# Micro_Controller.net
KiCad netlist of a schematic drawn in Altium Designer
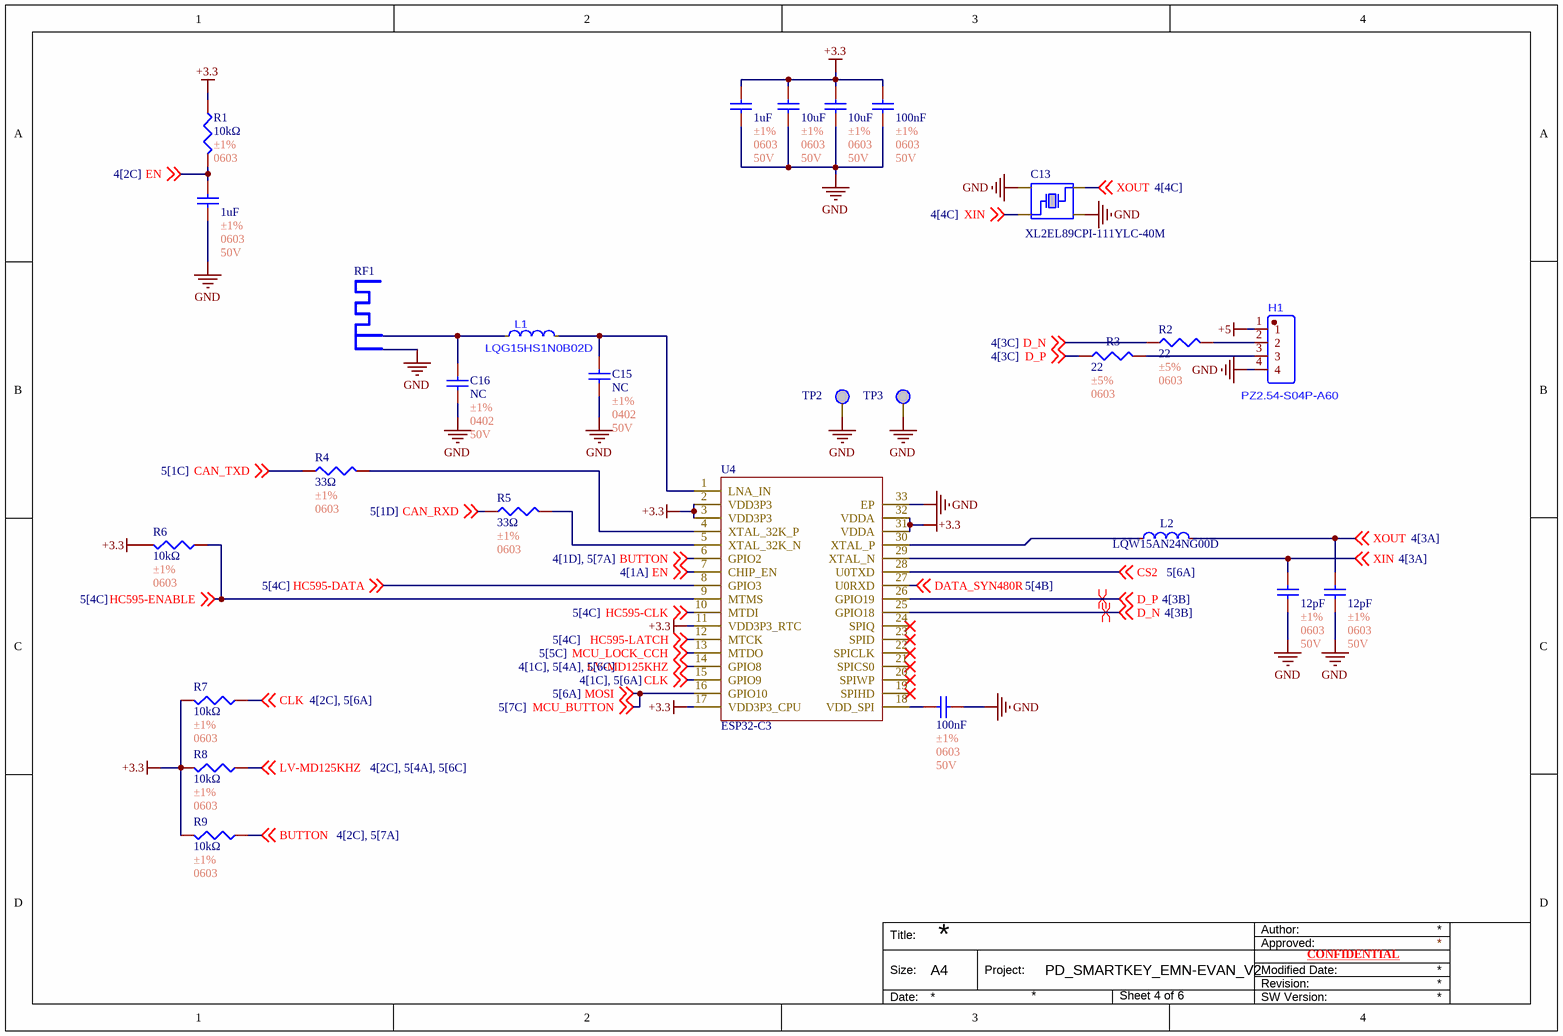
[diagram p0: Micro Controller.SchDoc]

(export (version "E")
  (design (tool "Eeschema 10.0.6"))
  (components
    (comp (ref "C9")
      (value "1uF")
      (footprint "C0603")
      (description "50V 10pF NP0 ±1% 0402 Multilayer Ceramic Capacitors MLCC - SMD/SMT ROHS")
      (fields
        (field (name "MANUFACTURER") "YAGEO")
        (field (name "MFR. PART #") "CC0402FRNPO9BN100")
        (field (name "TOLERANCE") "±1%")
        (field (name "PACKAGE") "0603")
        (field (name "VOLTAGE RATING") "50V")
      )
      (libsource (lib "Capital") (part "C0603_1uF_±1%"))
    )
    (comp (ref "C10")
      (value "10uF")
      (footprint "C0603")
      (description "50V 10pF NP0 ±1% 0402 Multilayer Ceramic Capacitors MLCC - SMD/SMT ROHS")
      (fields
        (field (name "MANUFACTURER") "YAGEO")
        (field (name "MFR. PART #") "CC0402FRNPO9BN100")
        (field (name "TOLERANCE") "±1%")
        (field (name "PACKAGE") "0603")
        (field (name "VOLTAGE RATING") "50V")
      )
      (libsource (lib "Capital") (part "C0603_10uF_±1%"))
    )
    (comp (ref "C11")
      (value "10uF")
      (footprint "C0603")
      (description "50V 10pF NP0 ±1% 0402 Multilayer Ceramic Capacitors MLCC - SMD/SMT ROHS")
      (fields
        (field (name "MANUFACTURER") "YAGEO")
        (field (name "MFR. PART #") "CC0402FRNPO9BN100")
        (field (name "TOLERANCE") "±1%")
        (field (name "PACKAGE") "0603")
        (field (name "VOLTAGE RATING") "50V")
      )
      (libsource (lib "Capital") (part "C0603_10uF_±1%"))
    )
    (comp (ref "C12")
      (value "100nF")
      (footprint "C0603")
      (description "50V 10pF NP0 ±1% 0402 Multilayer Ceramic Capacitors MLCC - SMD/SMT ROHS")
      (fields
        (field (name "MANUFACTURER") "YAGEO")
        (field (name "MFR. PART #") "CC0402FRNPO9BN100")
        (field (name "TOLERANCE") "±1%")
        (field (name "PACKAGE") "0603")
        (field (name "VOLTAGE RATING") "50V")
      )
      (libsource (lib "Capital") (part "C0603_100nF_±1%"))
    )
    (comp (ref "C13")
      (value "XL2EL89CPI-111YLC-40M")
      (footprint "XL2EL89CPI-111YLC-40M")
      (description "Crystal Oscillator 15pF SMD3225-4P Crystals RoHS")
      (fields (field (name "MANUFACTURER") "YXC Crystal Oscillators") (field (name "LCSC PART #") "C5444549"))
      (libsource (lib "Oscillator") (part "XL2EL89CPI-111YLC-40M"))
    )
    (comp (ref "C14")
      (value "1uF")
      (footprint "C0603")
      (description "50V 10pF NP0 ±1% 0402 Multilayer Ceramic Capacitors MLCC - SMD/SMT ROHS")
      (fields
        (field (name "MANUFACTURER") "YAGEO")
        (field (name "MFR. PART #") "CC0402FRNPO9BN100")
        (field (name "TOLERANCE") "±1%")
        (field (name "PACKAGE") "0603")
        (field (name "VOLTAGE RATING") "50V")
      )
      (libsource (lib "Capital") (part "C0603_1uF_±1%"))
    )
    (comp (ref "C15")
      (value "NC")
      (footprint "C0402")
      (fields
        (field (name "MANUFACTURER") "YAGEO")
        (field (name "MFR. PART #") "CC0402FRNPO9BN100")
        (field (name "LCSC PART #") "C513681")
        (field (name "TOLERANCE") "±1%")
        (field (name "PACKAGE") "0402")
        (field (name "VOLTAGE RATING") "50V")
      )
      (libsource (lib "Capital") (part "C0402_NC_±1%"))
    )
    (comp (ref "C16")
      (value "NC")
      (footprint "C0402")
      (fields
        (field (name "MANUFACTURER") "YAGEO")
        (field (name "MFR. PART #") "CC0402FRNPO9BN100")
        (field (name "LCSC PART #") "C513681")
        (field (name "TOLERANCE") "±1%")
        (field (name "PACKAGE") "0402")
        (field (name "VOLTAGE RATING") "50V")
      )
      (libsource (lib "Capital") (part "C0402_NC_±1%"))
    )
    (comp (ref "C17")
      (value "12pF")
      (footprint "C0603")
      (description "50V 10pF NP0 ±1% 0402 Multilayer Ceramic Capacitors MLCC - SMD/SMT ROHS")
      (fields
        (field (name "MANUFACTURER") "YAGEO")
        (field (name "MFR. PART #") "CC0402FRNPO9BN100")
        (field (name "TOLERANCE") "±1%")
        (field (name "PACKAGE") "0603")
        (field (name "VOLTAGE RATING") "50V")
      )
      (libsource (lib "Capital") (part "C0603_12pF_±1%"))
    )
    (comp (ref "C18")
      (value "12pF")
      (footprint "C0603")
      (description "50V 10pF NP0 ±1% 0402 Multilayer Ceramic Capacitors MLCC - SMD/SMT ROHS")
      (fields
        (field (name "MANUFACTURER") "YAGEO")
        (field (name "MFR. PART #") "CC0402FRNPO9BN100")
        (field (name "TOLERANCE") "±1%")
        (field (name "PACKAGE") "0603")
        (field (name "VOLTAGE RATING") "50V")
      )
      (libsource (lib "Capital") (part "C0603_12pF_±1%"))
    )
    (comp (ref "C19")
      (value "100nF")
      (footprint "C0603")
      (description "50V 10pF NP0 ±1% 0402 Multilayer Ceramic Capacitors MLCC - SMD/SMT ROHS")
      (fields
        (field (name "MANUFACTURER") "YAGEO")
        (field (name "MFR. PART #") "CC0402FRNPO9BN100")
        (field (name "TOLERANCE") "±1%")
        (field (name "PACKAGE") "0603")
        (field (name "VOLTAGE RATING") "50V")
      )
      (libsource (lib "Capital") (part "C0603_100nF_±1%"))
    )
    (comp (ref "H1")
      (value "PZ2.54-S04P-A60")
      (footprint "J_4P_XH2.54")
      (fields (field (name "MANUFACTURER") "JXTCONN") (field (name "LCSC PART #") "C42431795"))
      (libsource (lib "Header") (part "J_4P_XH2.54"))
    )
    (comp (ref "L1")
      (value "LQG15HS1N0B02D")
      (footprint "L0402_1nH")
      (description "FIXED IND 1nH 1A 70mΩ 0402")
      (fields (field (name "MANUFACTURER") "muRata") (field (name "LCSC PART #") "C162538"))
      (libsource (lib "Inductor") (part "L0402_1nH"))
    )
    (comp (ref "L2")
      (value "LQW15AN24NG00D")
      (footprint "LQW15AN24NG00D")
      (description "FIXED IND 24nH 280mA 520mΩ 0402")
      (fields (field (name "MANUFACTURER") "muRata") (field (name "LCSC PART #") "C167472"))
      (libsource (lib "Inductor") (part "LQW15AN24NG00D"))
    )
    (comp (ref "R1")
      (value "10kΩ")
      (footprint "R0603")
      (description "62.5mW Thick Film Resistor 50V ±1% ±200ppm/℃ 10Ω 0402 Chip Resistor - Surface Mount ROHS")
      (fields
        (field (name "MANUFACTURER") "YAGEO")
        (field (name "MFR. PART #") "RC0402FR-0710RL")
        (field (name "TOLERANCE") "±1%")
        (field (name "PACKAGE") "0603")
      )
      (libsource (lib "Resistor") (part "R0603_10kΩ_±1%"))
    )
    (comp (ref "R2")
      (value "22")
      (footprint "R0603")
      (description "100mW Thick Film Resistor 75V ±5% 0Ω 0603 Chip Resistor - Surface Mount ROHS")
      (fields
        (field (name "MANUFACTURER") "YAGEO")
        (field (name "MFR. PART #") "RC0603JR-070RL")
        (field (name "TOLERANCE") "±5%")
        (field (name "PACKAGE") "0603")
      )
      (libsource (lib "Resistor") (part "R0603_0Ω_±5%"))
    )
    (comp (ref "R3")
      (value "22")
      (footprint "R0603")
      (description "100mW Thick Film Resistor 75V ±5% 0Ω 0603 Chip Resistor - Surface Mount ROHS")
      (fields
        (field (name "MANUFACTURER") "YAGEO")
        (field (name "MFR. PART #") "RC0603JR-070RL")
        (field (name "TOLERANCE") "±5%")
        (field (name "PACKAGE") "0603")
      )
      (libsource (lib "Resistor") (part "R0603_0Ω_±5%"))
    )
    (comp (ref "R4")
      (value "33Ω")
      (footprint "R0603")
      (description "100mW Thick Film Resistor 75V ±1% ±200ppm/℃ 2Ω 0603 Chip Resistor - Surface Mount ROHS")
      (fields
        (field (name "MANUFACTURER") "YAGEO")
        (field (name "MFR. PART #") "RC0603FR-072RL")
        (field (name "TOLERANCE") "±1%")
        (field (name "PACKAGE") "0603")
      )
      (libsource (lib "Resistor") (part "R0603_33Ω_±5%"))
    )
    (comp (ref "R5")
      (value "33Ω")
      (footprint "R0603")
      (description "100mW Thick Film Resistor 75V ±1% ±200ppm/℃ 2Ω 0603 Chip Resistor - Surface Mount ROHS")
      (fields
        (field (name "MANUFACTURER") "YAGEO")
        (field (name "MFR. PART #") "RC0603FR-072RL")
        (field (name "TOLERANCE") "±1%")
        (field (name "PACKAGE") "0603")
      )
      (libsource (lib "Resistor") (part "R0603_33Ω_±5%"))
    )
    (comp (ref "R6")
      (value "10kΩ")
      (footprint "R0603")
      (description "62.5mW Thick Film Resistor 50V ±1% ±200ppm/℃ 10Ω 0402 Chip Resistor - Surface Mount ROHS")
      (fields
        (field (name "MANUFACTURER") "YAGEO")
        (field (name "MFR. PART #") "RC0402FR-0710RL")
        (field (name "TOLERANCE") "±1%")
        (field (name "PACKAGE") "0603")
      )
      (libsource (lib "Resistor") (part "R0603_10kΩ_±1%"))
    )
    (comp (ref "R7")
      (value "10kΩ")
      (footprint "R0603")
      (description "62.5mW Thick Film Resistor 50V ±1% ±200ppm/℃ 10Ω 0402 Chip Resistor - Surface Mount ROHS")
      (fields
        (field (name "MANUFACTURER") "YAGEO")
        (field (name "MFR. PART #") "RC0402FR-0710RL")
        (field (name "TOLERANCE") "±1%")
        (field (name "PACKAGE") "0603")
      )
      (libsource (lib "Resistor") (part "R0603_10kΩ_±1%"))
    )
    (comp (ref "R8")
      (value "10kΩ")
      (footprint "R0603")
      (description "62.5mW Thick Film Resistor 50V ±1% ±200ppm/℃ 10Ω 0402 Chip Resistor - Surface Mount ROHS")
      (fields
        (field (name "MANUFACTURER") "YAGEO")
        (field (name "MFR. PART #") "RC0402FR-0710RL")
        (field (name "TOLERANCE") "±1%")
        (field (name "PACKAGE") "0603")
      )
      (libsource (lib "Resistor") (part "R0603_10kΩ_±1%"))
    )
    (comp (ref "R9")
      (value "10kΩ")
      (footprint "R0603")
      (description "62.5mW Thick Film Resistor 50V ±1% ±200ppm/℃ 10Ω 0402 Chip Resistor - Surface Mount ROHS")
      (fields
        (field (name "MANUFACTURER") "YAGEO")
        (field (name "MFR. PART #") "RC0402FR-0710RL")
        (field (name "TOLERANCE") "±1%")
        (field (name "PACKAGE") "0603")
      )
      (libsource (lib "Resistor") (part "R0603_10kΩ_±1%"))
    )
    (comp (ref "RF1")
      (value "~")
      (footprint "2.4GHZ-50OHMS_v1.1")
      (libsource (lib "Antenna") (part "Antenna"))
    )
    (comp (ref "TP2") (value "TP") (footprint "TP") (libsource (lib "Other") (part "TP")))
    (comp (ref "TP3") (value "TP") (footprint "TP") (libsource (lib "Other") (part "TP")))
    (comp (ref "U4")
      (value "ESP32-C3")
      (footprint "ESP32-C3")
      (description "Others 160MHz QFN-32-EP(5x5) RF Transceiver Modules and Modems RoHS")
      (fields (field (name "MANUFACTURER") "ESPRESSIF") (field (name "LCSC PART #") "C2838500"))
      (libsource (lib "MCU") (part "ESP32-C3"))
    )
  )
  (nets
    (net (code "1") (name "+3.3") (class "Default")
      (node (ref "C10") (pin "1") (pinfunction "1_1") (pintype "passive"))
      (node (ref "C11") (pin "1") (pinfunction "1_1") (pintype "passive"))
      (node (ref "C12") (pin "1") (pinfunction "1_1") (pintype "passive"))
      (node (ref "C9") (pin "1") (pinfunction "1_1") (pintype "passive"))
      (node (ref "R1") (pin "1") (pinfunction "1_1") (pintype "passive"))
      (node (ref "R6") (pin "2") (pinfunction "2_2") (pintype "passive"))
      (node (ref "R7") (pin "2") (pinfunction "2_2") (pintype "passive"))
      (node (ref "R8") (pin "2") (pinfunction "2_2") (pintype "passive"))
      (node (ref "R9") (pin "2") (pinfunction "2_2") (pintype "passive"))
      (node (ref "U4") (pin "11") (pinfunction "VDD3P3_RTC_11") (pintype "passive"))
      (node (ref "U4") (pin "17") (pinfunction "VDD3P3_CPU_17") (pintype "passive"))
      (node (ref "U4") (pin "2") (pinfunction "VDD3P3_2") (pintype "passive"))
      (node (ref "U4") (pin "3") (pinfunction "VDD3P3_3") (pintype "passive"))
      (node (ref "U4") (pin "31") (pinfunction "VDDA_31") (pintype "passive"))
      (node (ref "U4") (pin "32") (pinfunction "VDDA_32") (pintype "passive"))
    )
    (net (code "2") (name "+5") (class "Default")
      (node (ref "H1") (pin "1") (pinfunction "1_1") (pintype "passive"))
    )
    (net (code "3") (name "BUTTON") (class "Default")
      (node (ref "R9") (pin "1") (pinfunction "1_1") (pintype "passive"))
      (node (ref "U4") (pin "6") (pinfunction "GPIO2_6") (pintype "passive"))
    )
    (net (code "4") (name "CAN_RXD") (class "Default")
      (node (ref "R5") (pin "1") (pinfunction "1_1") (pintype "passive"))
    )
    (net (code "5") (name "CAN_TXD") (class "Default")
      (node (ref "R4") (pin "1") (pinfunction "1_1") (pintype "passive"))
    )
    (net (code "6") (name "CLK") (class "Default")
      (node (ref "R7") (pin "1") (pinfunction "1_1") (pintype "passive"))
      (node (ref "U4") (pin "15") (pinfunction "GPIO9_15") (pintype "passive"))
    )
    (net (code "7") (name "CS2") (class "Default")
      (node (ref "U4") (pin "28") (pinfunction "U0TXD_28") (pintype "passive"))
    )
    (net (code "8") (name "DATA_SYN480R") (class "Default")
      (node (ref "U4") (pin "27") (pinfunction "U0RXD_27") (pintype "passive"))
    )
    (net (code "9") (name "D_N") (class "Default")
      (node (ref "R2") (pin "1") (pinfunction "1_1") (pintype "passive"))
      (node (ref "U4") (pin "25") (pinfunction "GPIO18_25") (pintype "passive"))
    )
    (net (code "10") (name "D_P") (class "Default")
      (node (ref "R3") (pin "1") (pinfunction "1_1") (pintype "passive"))
      (node (ref "U4") (pin "26") (pinfunction "GPIO19_26") (pintype "passive"))
    )
    (net (code "11") (name "EN") (class "Default")
      (node (ref "C14") (pin "1") (pinfunction "1_1") (pintype "passive"))
      (node (ref "R1") (pin "2") (pinfunction "2_2") (pintype "passive"))
      (node (ref "U4") (pin "7") (pinfunction "CHIP_EN_7") (pintype "passive"))
    )
    (net (code "12") (name "GND") (class "Default")
      (node (ref "C10") (pin "2") (pinfunction "2_2") (pintype "passive"))
      (node (ref "C11") (pin "2") (pinfunction "2_2") (pintype "passive"))
      (node (ref "C12") (pin "2") (pinfunction "2_2") (pintype "passive"))
      (node (ref "C13") (pin "2") (pinfunction "2_2") (pintype "passive"))
      (node (ref "C13") (pin "4") (pinfunction "4_4") (pintype "passive"))
      (node (ref "C14") (pin "2") (pinfunction "2_2") (pintype "passive"))
      (node (ref "C15") (pin "2") (pinfunction "2_2") (pintype "passive"))
      (node (ref "C16") (pin "2") (pinfunction "2_2") (pintype "passive"))
      (node (ref "C17") (pin "2") (pinfunction "2_2") (pintype "passive"))
      (node (ref "C18") (pin "2") (pinfunction "2_2") (pintype "passive"))
      (node (ref "C19") (pin "2") (pinfunction "2_2") (pintype "passive"))
      (node (ref "C9") (pin "2") (pinfunction "2_2") (pintype "passive"))
      (node (ref "H1") (pin "4") (pinfunction "4_4") (pintype "passive"))
      (node (ref "RF1") (pin "2") (pinfunction "2_2") (pintype "passive"))
      (node (ref "TP2") (pin "1") (pinfunction "1_1") (pintype "passive"))
      (node (ref "TP3") (pin "1") (pinfunction "1_1") (pintype "passive"))
      (node (ref "U4") (pin "33") (pinfunction "EP_33") (pintype "passive"))
    )
    (net (code "13") (name "HC595-CLK") (class "Default")
      (node (ref "U4") (pin "10") (pinfunction "MTDI_10") (pintype "passive"))
    )
    (net (code "14") (name "HC595-DATA") (class "Default")
      (node (ref "U4") (pin "8") (pinfunction "GPIO3_8") (pintype "passive"))
    )
    (net (code "15") (name "HC595-ENABLE") (class "Default")
      (node (ref "R6") (pin "1") (pinfunction "1_1") (pintype "passive"))
      (node (ref "U4") (pin "9") (pinfunction "MTMS_9") (pintype "passive"))
    )
    (net (code "16") (name "HC595-LATCH") (class "Default")
      (node (ref "U4") (pin "12") (pinfunction "MTCK_12") (pintype "passive"))
    )
    (net (code "17") (name "LV-MD125KHZ") (class "Default")
      (node (ref "R8") (pin "1") (pinfunction "1_1") (pintype "passive"))
      (node (ref "U4") (pin "14") (pinfunction "GPIO8_14") (pintype "passive"))
    )
    (net (code "18") (name "MCU_BUTTON") (class "Default")
      (node (ref "U4") (pin "16") (pinfunction "GPIO10_16") (pintype "passive"))
    )
    (net (code "19") (name "MCU_LOCK_CCH") (class "Default")
      (node (ref "U4") (pin "13") (pinfunction "MTDO_13") (pintype "passive"))
    )
    (net (code "20") (name "Net-(C16-Pad1)") (class "Default")
      (node (ref "C16") (pin "1") (pinfunction "1_1") (pintype "passive"))
      (node (ref "L1") (pin "1") (pinfunction "1_1") (pintype "passive"))
      (node (ref "RF1") (pin "1") (pinfunction "1_1") (pintype "passive"))
    )
    (net (code "21") (name "Net-(H1-Pad2)") (class "Default")
      (node (ref "H1") (pin "2") (pinfunction "2_2") (pintype "passive"))
      (node (ref "R2") (pin "2") (pinfunction "2_2") (pintype "passive"))
    )
    (net (code "22") (name "Net-(H1-Pad3)") (class "Default")
      (node (ref "H1") (pin "3") (pinfunction "3_3") (pintype "passive"))
      (node (ref "R3") (pin "2") (pinfunction "2_2") (pintype "passive"))
    )
    (net (code "23") (name "Net-(U4-LNA_IN)") (class "Default")
      (node (ref "C15") (pin "1") (pinfunction "1_1") (pintype "passive"))
      (node (ref "L1") (pin "2") (pinfunction "2_2") (pintype "passive"))
      (node (ref "U4") (pin "1") (pinfunction "LNA_IN_1") (pintype "passive"))
    )
    (net (code "24") (name "Net-(U4-VDD_SPI)") (class "Default")
      (node (ref "C19") (pin "1") (pinfunction "1_1") (pintype "passive"))
      (node (ref "U4") (pin "18") (pinfunction "VDD_SPI_18") (pintype "passive"))
    )
    (net (code "25") (name "Net-(U4-XTAL_32K_N)") (class "Default")
      (node (ref "R5") (pin "2") (pinfunction "2_2") (pintype "passive"))
      (node (ref "U4") (pin "5") (pinfunction "XTAL_32K_N_5") (pintype "passive"))
    )
    (net (code "26") (name "Net-(U4-XTAL_32K_P)") (class "Default")
      (node (ref "R4") (pin "2") (pinfunction "2_2") (pintype "passive"))
      (node (ref "U4") (pin "4") (pinfunction "XTAL_32K_P_4") (pintype "passive"))
    )
    (net (code "27") (name "Net-(U4-XTAL_P)") (class "Default")
      (node (ref "L2") (pin "1") (pinfunction "1_1") (pintype "passive"))
      (node (ref "U4") (pin "30") (pinfunction "XTAL_P_30") (pintype "passive"))
    )
    (net (code "28") (name "XIN") (class "Default")
      (node (ref "C13") (pin "1") (pinfunction "1_1") (pintype "passive"))
      (node (ref "C17") (pin "1") (pinfunction "1_1") (pintype "passive"))
      (node (ref "U4") (pin "29") (pinfunction "XTAL_N_29") (pintype "passive"))
    )
    (net (code "29") (name "XOUT") (class "Default")
      (node (ref "C13") (pin "3") (pinfunction "3_3") (pintype "passive"))
      (node (ref "C18") (pin "1") (pinfunction "1_1") (pintype "passive"))
      (node (ref "L2") (pin "2") (pinfunction "2_2") (pintype "passive"))
    )
    (net (code "30") (name "unconnected-(U4-SPICLK-Pad22)") (class "Default")
      (node (ref "U4") (pin "22") (pinfunction "SPICLK_22") (pintype "passive+no_connect"))
    )
    (net (code "31") (name "unconnected-(U4-SPICS0-Pad21)") (class "Default")
      (node (ref "U4") (pin "21") (pinfunction "SPICS0_21") (pintype "passive+no_connect"))
    )
    (net (code "32") (name "unconnected-(U4-SPID-Pad23)") (class "Default")
      (node (ref "U4") (pin "23") (pinfunction "SPID_23") (pintype "passive+no_connect"))
    )
    (net (code "33") (name "unconnected-(U4-SPIHD-Pad19)") (class "Default")
      (node (ref "U4") (pin "19") (pinfunction "SPIHD_19") (pintype "passive+no_connect"))
    )
    (net (code "34") (name "unconnected-(U4-SPIQ-Pad24)") (class "Default")
      (node (ref "U4") (pin "24") (pinfunction "SPIQ_24") (pintype "passive+no_connect"))
    )
    (net (code "35") (name "unconnected-(U4-SPIWP-Pad20)") (class "Default")
      (node (ref "U4") (pin "20") (pinfunction "SPIWP_20") (pintype "passive+no_connect"))
    )
  )
)
